# Non-Contact_Switch_v1.net
KiCad netlist of a schematic drawn in EAGLE
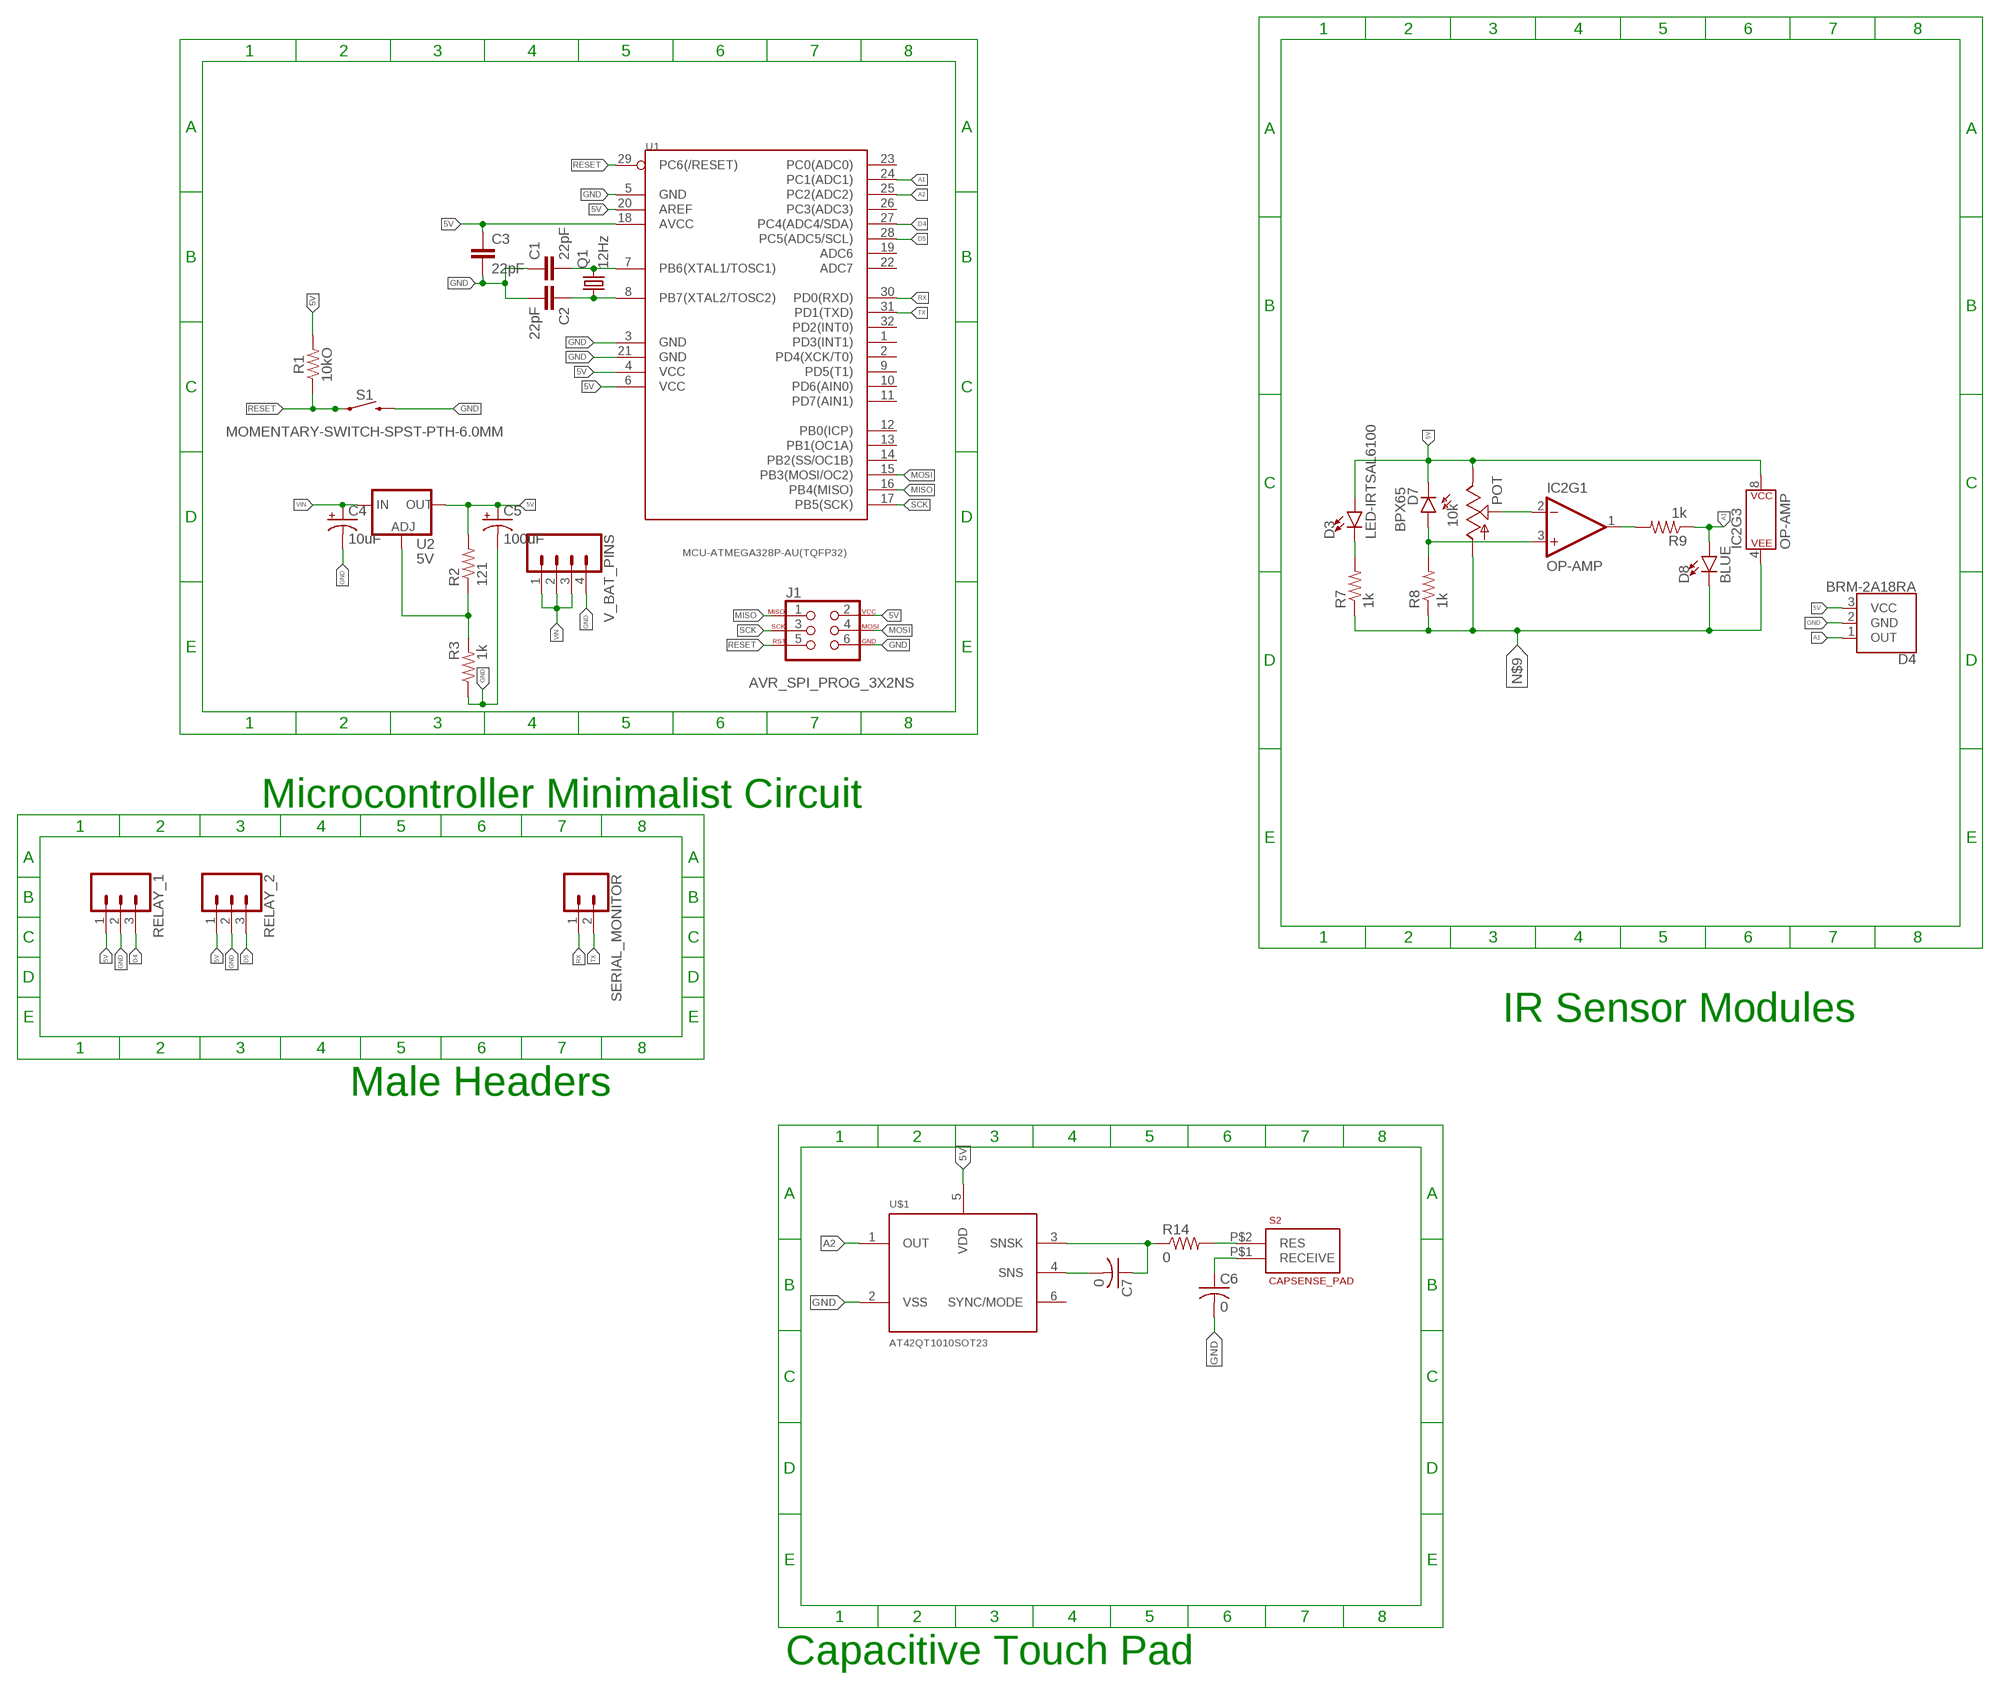
[diagram p0: schematic, sheet 1]

(export (version "E")
  (design (tool "Eeschema 10.0.6"))
  (components
    (comp (ref "C1")
      (value "22pF")
      (footprint "eagle-import:C0603")
      (libsource (lib "eagle-import") (part "C-EUC0603"))
    )
    (comp (ref "C2")
      (value "22pF")
      (footprint "eagle-import:C0603")
      (libsource (lib "eagle-import") (part "C-EUC0603"))
    )
    (comp (ref "C3")
      (value "22pF")
      (footprint "eagle-import:C0603")
      (libsource (lib "eagle-import") (part "C-EUC0603"))
    )
    (comp (ref "C4")
      (value "10uF")
      (footprint "eagle-import:0603-POLAR")
      (libsource (lib "eagle-import") (part "10UF-POLAR-0603-6.3V-20%(TANT)"))
    )
    (comp (ref "C5")
      (value "100uF")
      (footprint "eagle-import:0603-POLAR")
      (libsource (lib "eagle-import") (part "10UF-POLAR-0603-6.3V-20%(TANT)"))
    )
    (comp (ref "C6")
      (value "0")
      (footprint "eagle-import:C0603K")
      (libsource (lib "eagle-import") (part "C-USC0603K"))
    )
    (comp (ref "C7")
      (value "0")
      (footprint "eagle-import:C0603K")
      (libsource (lib "eagle-import") (part "C-USC0603K"))
    )
    (comp (ref "D3")
      (value "LED-IRTSAL6100")
      (footprint "eagle-import:LED_5MM")
      (libsource (lib "eagle-import") (part "LED-IRTSAL6100"))
    )
    (comp (ref "D4")
      (value "BRM-2A18RA")
      (footprint "eagle-import:BRM-2508")
      (libsource (lib "eagle-import") (part "BRM-2A18RA"))
    )
    (comp (ref "D7")
      (value "BPX65")
      (footprint "eagle-import:BPX65")
      (fields (field (name "MPN") "BPX65."))
      (libsource (lib "eagle-import") (part "BPX65"))
    )
    (comp (ref "D8")
      (value "BLUE")
      (footprint "eagle-import:LED-0603")
      (libsource (lib "eagle-import") (part "LED-BLUE0603"))
    )
    (comp (ref "IC2")
      (value "OP-AMP")
      (footprint "eagle-import:SO08")
      (libsource (lib "eagle-import") (part "OPAMP-DUALU"))
    )
    (comp (ref "J1")
      (value "AVR_SPI_PROG_3X2NS")
      (footprint "eagle-import:2X3-NS")
      (libsource (lib "eagle-import") (part "AVR_SPI_PROG_3X2NS"))
    )
    (comp (ref "POT")
      (value "10k")
      (footprint "eagle-import:PT-10")
      (libsource (lib "eagle-import") (part "TRIM_US-PT10"))
    )
    (comp (ref "Q1")
      (value "12Hz")
      (footprint "eagle-import:HC49UP")
      (libsource (lib "eagle-import") (part "CRYSTALHC49UP"))
    )
    (comp (ref "R1")
      (value "10kO")
      (footprint "eagle-import:0603")
      (libsource (lib "eagle-import") (part "1.8MOHM"))
    )
    (comp (ref "R2")
      (value "121")
      (footprint "eagle-import:R0603")
      (libsource (lib "eagle-import") (part "R-US_R0603"))
    )
    (comp (ref "R3")
      (value "1k")
      (footprint "eagle-import:R0603")
      (libsource (lib "eagle-import") (part "R-US_R0603"))
    )
    (comp (ref "R7")
      (value "1k")
      (footprint "eagle-import:R0603")
      (libsource (lib "eagle-import") (part "R-US_R0603"))
    )
    (comp (ref "R8")
      (value "1k")
      (footprint "eagle-import:R0603")
      (libsource (lib "eagle-import") (part "R-US_R0603"))
    )
    (comp (ref "R9")
      (value "1k")
      (footprint "eagle-import:R0603")
      (libsource (lib "eagle-import") (part "R-US_R0603"))
    )
    (comp (ref "R14")
      (value "0")
      (footprint "eagle-import:R0603")
      (libsource (lib "eagle-import") (part "R-US_R0603"))
    )
    (comp (ref "RELAY_1")
      (value "CONN_031X03_NO_SILK")
      (footprint "eagle-import:1X03_NO_SILK")
      (libsource (lib "eagle-import") (part "CONN_031X03_NO_SILK"))
    )
    (comp (ref "RELAY_2")
      (value "CONN_031X03_NO_SILK")
      (footprint "eagle-import:1X03_NO_SILK")
      (libsource (lib "eagle-import") (part "CONN_031X03_NO_SILK"))
    )
    (comp (ref "S1")
      (value "MOMENTARY-SWITCH-SPST-PTH-6.0MM")
      (footprint "eagle-import:TACTILE_SWITCH_PTH_6.0MM")
      (libsource (lib "eagle-import") (part "MOMENTARY-SWITCH-SPST-PTH-6.0MM"))
    )
    (comp (ref "S2")
      (value "CAPSENSE_PAD")
      (footprint "eagle-import:CAPSENSE_PAD")
      (libsource (lib "eagle-import") (part "CAPSENSE_PAD"))
    )
    (comp (ref "SERIAL_MONITOR")
      (value "CONN_02")
      (footprint "eagle-import:1X02")
      (libsource (lib "eagle-import") (part "CONN_02"))
    )
    (comp (ref "U$1")
      (value "AT42QT1010SOT23")
      (footprint "eagle-import:SOT23-6")
      (libsource (lib "eagle-import") (part "AT42QT1010SOT23"))
    )
    (comp (ref "U1")
      (value "MCU-ATMEGA328P-AU(TQFP32)")
      (footprint "eagle-import:TQFP32-0.8-7X7MM")
      (fields (field (name "MF") "Microchip") (field (name "MP") "ATMEGA328P-AU"))
      (libsource (lib "eagle-import") (part "MCU-ATMEGA328P-AU(TQFP32)"))
    )
    (comp (ref "U2")
      (value "5V")
      (footprint "eagle-import:SOT223")
      (libsource (lib "eagle-import") (part "V_REG_LM1117SOT223"))
    )
    (comp (ref "V_BAT_PINS")
      (value "CONN_04LOCK")
      (footprint "eagle-import:1X04_LOCK")
      (libsource (lib "eagle-import") (part "CONN_04LOCK"))
    )
  )
  (nets
    (net (code "1") (name "5V") (class "Default")
      (node (ref "C3") (pin "1") (pinfunction "1_1") (pintype "passive"))
      (node (ref "C5") (pin "+") (pinfunction "+_+") (pintype "passive"))
      (node (ref "D3") (pin "A") (pinfunction "A_A") (pintype "passive"))
      (node (ref "D4") (pin "3") (pinfunction "VCC_3") (pintype "bidirectional"))
      (node (ref "D7") (pin "K") (pinfunction "C_K") (pintype "passive"))
      (node (ref "IC2") (pin "8") (pinfunction "P$V+_8") (pintype "bidirectional"))
      (node (ref "J1") (pin "2") (pinfunction "2_2") (pintype "passive"))
      (node (ref "POT") (pin "E") (pinfunction "E_E") (pintype "passive"))
      (node (ref "R1") (pin "2") (pinfunction "2_2") (pintype "passive"))
      (node (ref "R2") (pin "2") (pinfunction "2_2") (pintype "passive"))
      (node (ref "RELAY_1") (pin "1") (pinfunction "1_1") (pintype "passive"))
      (node (ref "RELAY_2") (pin "1") (pinfunction "1_1") (pintype "passive"))
      (node (ref "U$1") (pin "5") (pinfunction "VDD_5") (pintype "bidirectional"))
      (node (ref "U1") (pin "18") (pinfunction "AVCC_18") (pintype "bidirectional"))
      (node (ref "U1") (pin "20") (pinfunction "AREF_20") (pintype "bidirectional"))
      (node (ref "U1") (pin "4") (pinfunction "VCC_4") (pintype "bidirectional"))
      (node (ref "U1") (pin "6") (pinfunction "VCC_6") (pintype "bidirectional"))
      (node (ref "U2") (pin "2") (pinfunction "OUT_2") (pintype "output"))
      (node (ref "U2") (pin "4") (pinfunction "OUT_4") (pintype "output"))
    )
    (net (code "2") (name "A1") (class "Default")
      (node (ref "D4") (pin "1") (pinfunction "OUT_1") (pintype "bidirectional"))
      (node (ref "D8") (pin "A") (pinfunction "A_A") (pintype "passive"))
      (node (ref "R9") (pin "1") (pinfunction "1_1") (pintype "passive"))
      (node (ref "U1") (pin "24") (pinfunction "PC1(ADC1)_24") (pintype "bidirectional"))
    )
    (net (code "3") (name "A2") (class "Default")
      (node (ref "U$1") (pin "1") (pinfunction "OUT_1") (pintype "bidirectional"))
      (node (ref "U1") (pin "25") (pinfunction "PC2(ADC2)_25") (pintype "bidirectional"))
    )
    (net (code "4") (name "D4") (class "Default")
      (node (ref "RELAY_1") (pin "3") (pinfunction "3_3") (pintype "passive"))
      (node (ref "U1") (pin "27") (pinfunction "PC4(ADC4/SDA)_27") (pintype "bidirectional"))
    )
    (net (code "5") (name "D5") (class "Default")
      (node (ref "RELAY_2") (pin "3") (pinfunction "3_3") (pintype "passive"))
      (node (ref "U1") (pin "28") (pinfunction "PC5(ADC5/SCL)_28") (pintype "bidirectional"))
    )
    (net (code "6") (name "GND") (class "Default")
      (node (ref "C1") (pin "1") (pinfunction "1_1") (pintype "passive"))
      (node (ref "C2") (pin "2") (pinfunction "2_2") (pintype "passive"))
      (node (ref "C3") (pin "2") (pinfunction "2_2") (pintype "passive"))
      (node (ref "C4") (pin "-") (pinfunction "-_-") (pintype "passive"))
      (node (ref "C5") (pin "-") (pinfunction "-_-") (pintype "passive"))
      (node (ref "C6") (pin "2") (pinfunction "2_2") (pintype "passive"))
      (node (ref "D4") (pin "2") (pinfunction "GND_2") (pintype "bidirectional"))
      (node (ref "IC2") (pin "2") (pinfunction "-IN_2") (pintype "input"))
      (node (ref "J1") (pin "6") (pinfunction "6_6") (pintype "passive"))
      (node (ref "POT") (pin "S") (pinfunction "S_S") (pintype "passive"))
      (node (ref "R3") (pin "1") (pinfunction "1_1") (pintype "passive"))
      (node (ref "RELAY_1") (pin "2") (pinfunction "2_2") (pintype "passive"))
      (node (ref "RELAY_2") (pin "2") (pinfunction "2_2") (pintype "passive"))
      (node (ref "S1") (pin "3") (pinfunction "2_3") (pintype "passive"))
      (node (ref "U$1") (pin "2") (pinfunction "VSS_2") (pintype "bidirectional"))
      (node (ref "U1") (pin "21") (pinfunction "GND_21") (pintype "bidirectional"))
      (node (ref "U1") (pin "3") (pinfunction "GND_3") (pintype "bidirectional"))
      (node (ref "U1") (pin "5") (pinfunction "GND_5") (pintype "bidirectional"))
      (node (ref "V_BAT_PINS") (pin "4") (pinfunction "4_4") (pintype "passive"))
    )
    (net (code "7") (name "MISO") (class "Default")
      (node (ref "J1") (pin "1") (pinfunction "1_1") (pintype "passive"))
      (node (ref "U1") (pin "16") (pinfunction "PB4(MISO)_16") (pintype "bidirectional"))
    )
    (net (code "8") (name "MOSI") (class "Default")
      (node (ref "J1") (pin "4") (pinfunction "4_4") (pintype "passive"))
      (node (ref "U1") (pin "15") (pinfunction "PB3(MOSI/OC2)_15") (pintype "bidirectional"))
    )
    (net (code "9") (name "N$9") (class "Default")
      (node (ref "D8") (pin "C") (pinfunction "C_C") (pintype "passive"))
      (node (ref "IC2") (pin "4") (pinfunction "P$V-_4") (pintype "bidirectional"))
      (node (ref "POT") (pin "A") (pinfunction "A_A") (pintype "passive"))
      (node (ref "R7") (pin "1") (pinfunction "1_1") (pintype "passive"))
      (node (ref "R8") (pin "1") (pinfunction "1_1") (pintype "passive"))
    )
    (net (code "10") (name "Net-(D3-C)") (class "Default")
      (node (ref "D3") (pin "K") (pinfunction "C_K") (pintype "passive"))
      (node (ref "R7") (pin "2") (pinfunction "2_2") (pintype "passive"))
    )
    (net (code "11") (name "Net-(IC2A-+IN)") (class "Default")
      (node (ref "D7") (pin "A") (pinfunction "A_A") (pintype "passive"))
      (node (ref "IC2") (pin "3") (pinfunction "+IN_3") (pintype "input"))
      (node (ref "R8") (pin "2") (pinfunction "2_2") (pintype "passive"))
    )
    (net (code "12") (name "Net-(IC2A-OUT)") (class "Default")
      (node (ref "IC2") (pin "1") (pinfunction "OUT_1") (pintype "output"))
      (node (ref "R9") (pin "2") (pinfunction "2_2") (pintype "passive"))
    )
    (net (code "13") (name "Net-(S2-RECEIVE)") (class "Default")
      (node (ref "C6") (pin "1") (pinfunction "1_1") (pintype "passive"))
      (node (ref "S2") (pin "P$1") (pinfunction "RECEIVE_P$1") (pintype "bidirectional"))
    )
    (net (code "14") (name "Net-(S2-RES)") (class "Default")
      (node (ref "R14") (pin "2") (pinfunction "2_2") (pintype "passive"))
      (node (ref "S2") (pin "P$2") (pinfunction "RES_P$2") (pintype "bidirectional"))
    )
    (net (code "15") (name "Net-(U$1-SNS)") (class "Default")
      (node (ref "C7") (pin "2") (pinfunction "2_2") (pintype "passive"))
      (node (ref "U$1") (pin "4") (pinfunction "SNS_4") (pintype "bidirectional"))
    )
    (net (code "16") (name "Net-(U$1-SNSK)") (class "Default")
      (node (ref "C7") (pin "1") (pinfunction "1_1") (pintype "passive"))
      (node (ref "R14") (pin "1") (pinfunction "1_1") (pintype "passive"))
      (node (ref "U$1") (pin "3") (pinfunction "SNSK_3") (pintype "bidirectional"))
    )
    (net (code "17") (name "Net-(U1-PB6(XTAL1{slash}TOSC1))") (class "Default")
      (node (ref "C1") (pin "2") (pinfunction "2_2") (pintype "passive"))
      (node (ref "Q1") (pin "2") (pinfunction "2_2") (pintype "passive"))
      (node (ref "U1") (pin "7") (pinfunction "PB6(XTAL1/TOSC1)_7") (pintype "bidirectional"))
    )
    (net (code "18") (name "Net-(U1-PB7(XTAL2{slash}TOSC2))") (class "Default")
      (node (ref "C2") (pin "1") (pinfunction "1_1") (pintype "passive"))
      (node (ref "Q1") (pin "1") (pinfunction "1_1") (pintype "passive"))
      (node (ref "U1") (pin "8") (pinfunction "PB7(XTAL2/TOSC2)_8") (pintype "bidirectional"))
    )
    (net (code "19") (name "Net-(U2-ADJ)") (class "Default")
      (node (ref "R2") (pin "1") (pinfunction "1_1") (pintype "passive"))
      (node (ref "R3") (pin "2") (pinfunction "2_2") (pintype "passive"))
      (node (ref "U2") (pin "1") (pinfunction "ADJ_1") (pintype "input"))
    )
    (net (code "20") (name "RESET") (class "Default")
      (node (ref "J1") (pin "5") (pinfunction "5_5") (pintype "passive"))
      (node (ref "R1") (pin "1") (pinfunction "1_1") (pintype "passive"))
      (node (ref "S1") (pin "1") (pinfunction "1_1") (pintype "passive"))
      (node (ref "U1") (pin "29") (pinfunction "PC6(/RESET)_29") (pintype "bidirectional"))
    )
    (net (code "21") (name "RX") (class "Default")
      (node (ref "SERIAL_MONITOR") (pin "1") (pinfunction "1_1") (pintype "passive"))
      (node (ref "U1") (pin "30") (pinfunction "PD0(RXD)_30") (pintype "bidirectional"))
    )
    (net (code "22") (name "SCK") (class "Default")
      (node (ref "J1") (pin "3") (pinfunction "3_3") (pintype "passive"))
      (node (ref "U1") (pin "17") (pinfunction "PB5(SCK)_17") (pintype "bidirectional"))
    )
    (net (code "23") (name "TX") (class "Default")
      (node (ref "SERIAL_MONITOR") (pin "2") (pinfunction "2_2") (pintype "passive"))
      (node (ref "U1") (pin "31") (pinfunction "PD1(TXD)_31") (pintype "bidirectional"))
    )
    (net (code "24") (name "VIN") (class "Default")
      (node (ref "C4") (pin "+") (pinfunction "+_+") (pintype "passive"))
      (node (ref "U2") (pin "3") (pinfunction "IN_3") (pintype "input"))
      (node (ref "V_BAT_PINS") (pin "1") (pinfunction "1_1") (pintype "passive"))
      (node (ref "V_BAT_PINS") (pin "2") (pinfunction "2_2") (pintype "passive"))
      (node (ref "V_BAT_PINS") (pin "3") (pinfunction "3_3") (pintype "passive"))
    )
    (net (code "25") (name "unconnected-(U$1-SYNC{slash}MODE-Pad6)") (class "Default")
      (node (ref "U$1") (pin "6") (pinfunction "SYNC/MODE_6") (pintype "bidirectional"))
    )
    (net (code "26") (name "unconnected-(U1-ADC6-Pad19)") (class "Default")
      (node (ref "U1") (pin "19") (pinfunction "ADC6_19") (pintype "bidirectional"))
    )
    (net (code "27") (name "unconnected-(U1-ADC7-Pad22)") (class "Default")
      (node (ref "U1") (pin "22") (pinfunction "ADC7_22") (pintype "bidirectional"))
    )
    (net (code "28") (name "unconnected-(U1-PB0(ICP)-Pad12)") (class "Default")
      (node (ref "U1") (pin "12") (pinfunction "PB0(ICP)_12") (pintype "bidirectional"))
    )
    (net (code "29") (name "unconnected-(U1-PB1(OC1A)-Pad13)") (class "Default")
      (node (ref "U1") (pin "13") (pinfunction "PB1(OC1A)_13") (pintype "bidirectional"))
    )
    (net (code "30") (name "unconnected-(U1-PB2(SS{slash}OC1B)-Pad14)") (class "Default")
      (node (ref "U1") (pin "14") (pinfunction "PB2(SS/OC1B)_14") (pintype "bidirectional"))
    )
    (net (code "31") (name "unconnected-(U1-PC0(ADC0)-Pad23)") (class "Default")
      (node (ref "U1") (pin "23") (pinfunction "PC0(ADC0)_23") (pintype "bidirectional"))
    )
    (net (code "32") (name "unconnected-(U1-PC3(ADC3)-Pad26)") (class "Default")
      (node (ref "U1") (pin "26") (pinfunction "PC3(ADC3)_26") (pintype "bidirectional"))
    )
    (net (code "33") (name "unconnected-(U1-PD2(INT0)-Pad32)") (class "Default")
      (node (ref "U1") (pin "32") (pinfunction "PD2(INT0)_32") (pintype "bidirectional"))
    )
    (net (code "34") (name "unconnected-(U1-PD3(INT1)-Pad1)") (class "Default")
      (node (ref "U1") (pin "1") (pinfunction "PD3(INT1)_1") (pintype "bidirectional"))
    )
    (net (code "35") (name "unconnected-(U1-PD4(XCK{slash}T0)-Pad2)") (class "Default")
      (node (ref "U1") (pin "2") (pinfunction "PD4(XCK/T0)_2") (pintype "bidirectional"))
    )
    (net (code "36") (name "unconnected-(U1-PD5(T1)-Pad9)") (class "Default")
      (node (ref "U1") (pin "9") (pinfunction "PD5(T1)_9") (pintype "bidirectional"))
    )
    (net (code "37") (name "unconnected-(U1-PD6(AIN0)-Pad10)") (class "Default")
      (node (ref "U1") (pin "10") (pinfunction "PD6(AIN0)_10") (pintype "bidirectional"))
    )
    (net (code "38") (name "unconnected-(U1-PD7(AIN1)-Pad11)") (class "Default")
      (node (ref "U1") (pin "11") (pinfunction "PD7(AIN1)_11") (pintype "bidirectional"))
    )
  )
)
